# untitled.net
KiCad netlist of a schematic drawn in EAGLE
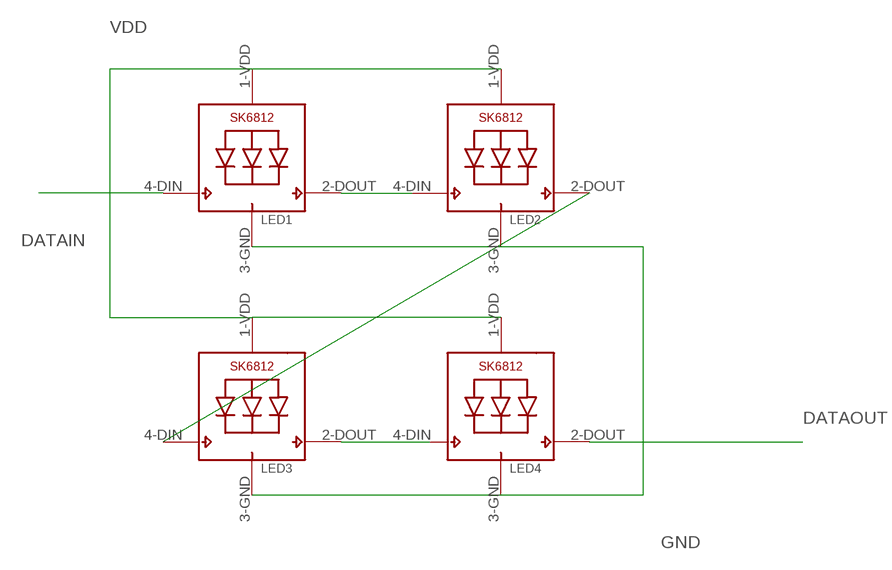
[diagram p0: schematic, sheet 1]

(export (version "E")
  (design (tool "Eeschema 10.0.6"))
  (components
    (comp (ref "LED1")
      (value "SK6812_5050W")
      (footprint "eagle-import:LED5050_W")
      (libsource (lib "eagle-import") (part "SK6812_5050W"))
    )
    (comp (ref "LED2")
      (value "SK6812_5050W")
      (footprint "eagle-import:LED5050_W")
      (libsource (lib "eagle-import") (part "SK6812_5050W"))
    )
    (comp (ref "LED3")
      (value "SK6812_5050W")
      (footprint "eagle-import:LED5050_W")
      (libsource (lib "eagle-import") (part "SK6812_5050W"))
    )
    (comp (ref "LED4")
      (value "SK6812_5050W")
      (footprint "eagle-import:LED5050_W")
      (libsource (lib "eagle-import") (part "SK6812_5050W"))
    )
  )
  (nets
    (net (code "1") (name "/DATAIN") (class "Default")
      (node (ref "LED1") (pin "4-DIN") (pinfunction "DI_4-DIN") (pintype "input"))
    )
    (net (code "2") (name "/DATAOUT") (class "Default")
      (node (ref "LED4") (pin "2-DOUT") (pinfunction "DO_2-DOUT") (pintype "output"))
    )
    (net (code "3") (name "/GND") (class "Default")
      (node (ref "LED1") (pin "3-GND") (pinfunction "GND_3-GND") (pintype "power_in"))
      (node (ref "LED2") (pin "3-GND") (pinfunction "GND_3-GND") (pintype "power_in"))
      (node (ref "LED3") (pin "3-GND") (pinfunction "GND_3-GND") (pintype "power_in"))
      (node (ref "LED4") (pin "3-GND") (pinfunction "GND_3-GND") (pintype "power_in"))
    )
    (net (code "4") (name "/VDD") (class "Default")
      (node (ref "LED1") (pin "1-VDD") (pinfunction "VDD_1-VDD") (pintype "power_in"))
      (node (ref "LED2") (pin "1-VDD") (pinfunction "VDD_1-VDD") (pintype "power_in"))
      (node (ref "LED3") (pin "1-VDD") (pinfunction "VDD_1-VDD") (pintype "power_in"))
      (node (ref "LED4") (pin "1-VDD") (pinfunction "VDD_1-VDD") (pintype "power_in"))
    )
    (net (code "5") (name "Net-(LED1-DO)") (class "Default")
      (node (ref "LED1") (pin "2-DOUT") (pinfunction "DO_2-DOUT") (pintype "output"))
      (node (ref "LED2") (pin "4-DIN") (pinfunction "DI_4-DIN") (pintype "input"))
    )
    (net (code "6") (name "Net-(LED2-DO)") (class "Default")
      (node (ref "LED2") (pin "2-DOUT") (pinfunction "DO_2-DOUT") (pintype "output"))
      (node (ref "LED3") (pin "4-DIN") (pinfunction "DI_4-DIN") (pintype "input"))
    )
    (net (code "7") (name "unconnected-(LED3-DO-Pad2-DOUT)") (class "Default")
      (node (ref "LED3") (pin "2-DOUT") (pinfunction "DO_2-DOUT") (pintype "output"))
    )
    (net (code "8") (name "unconnected-(LED4-DI-Pad4-DIN)") (class "Default")
      (node (ref "LED4") (pin "4-DIN") (pinfunction "DI_4-DIN") (pintype "input"))
    )
  )
)
